# expansion.net
KiCad netlist of a schematic drawn in EAGLE
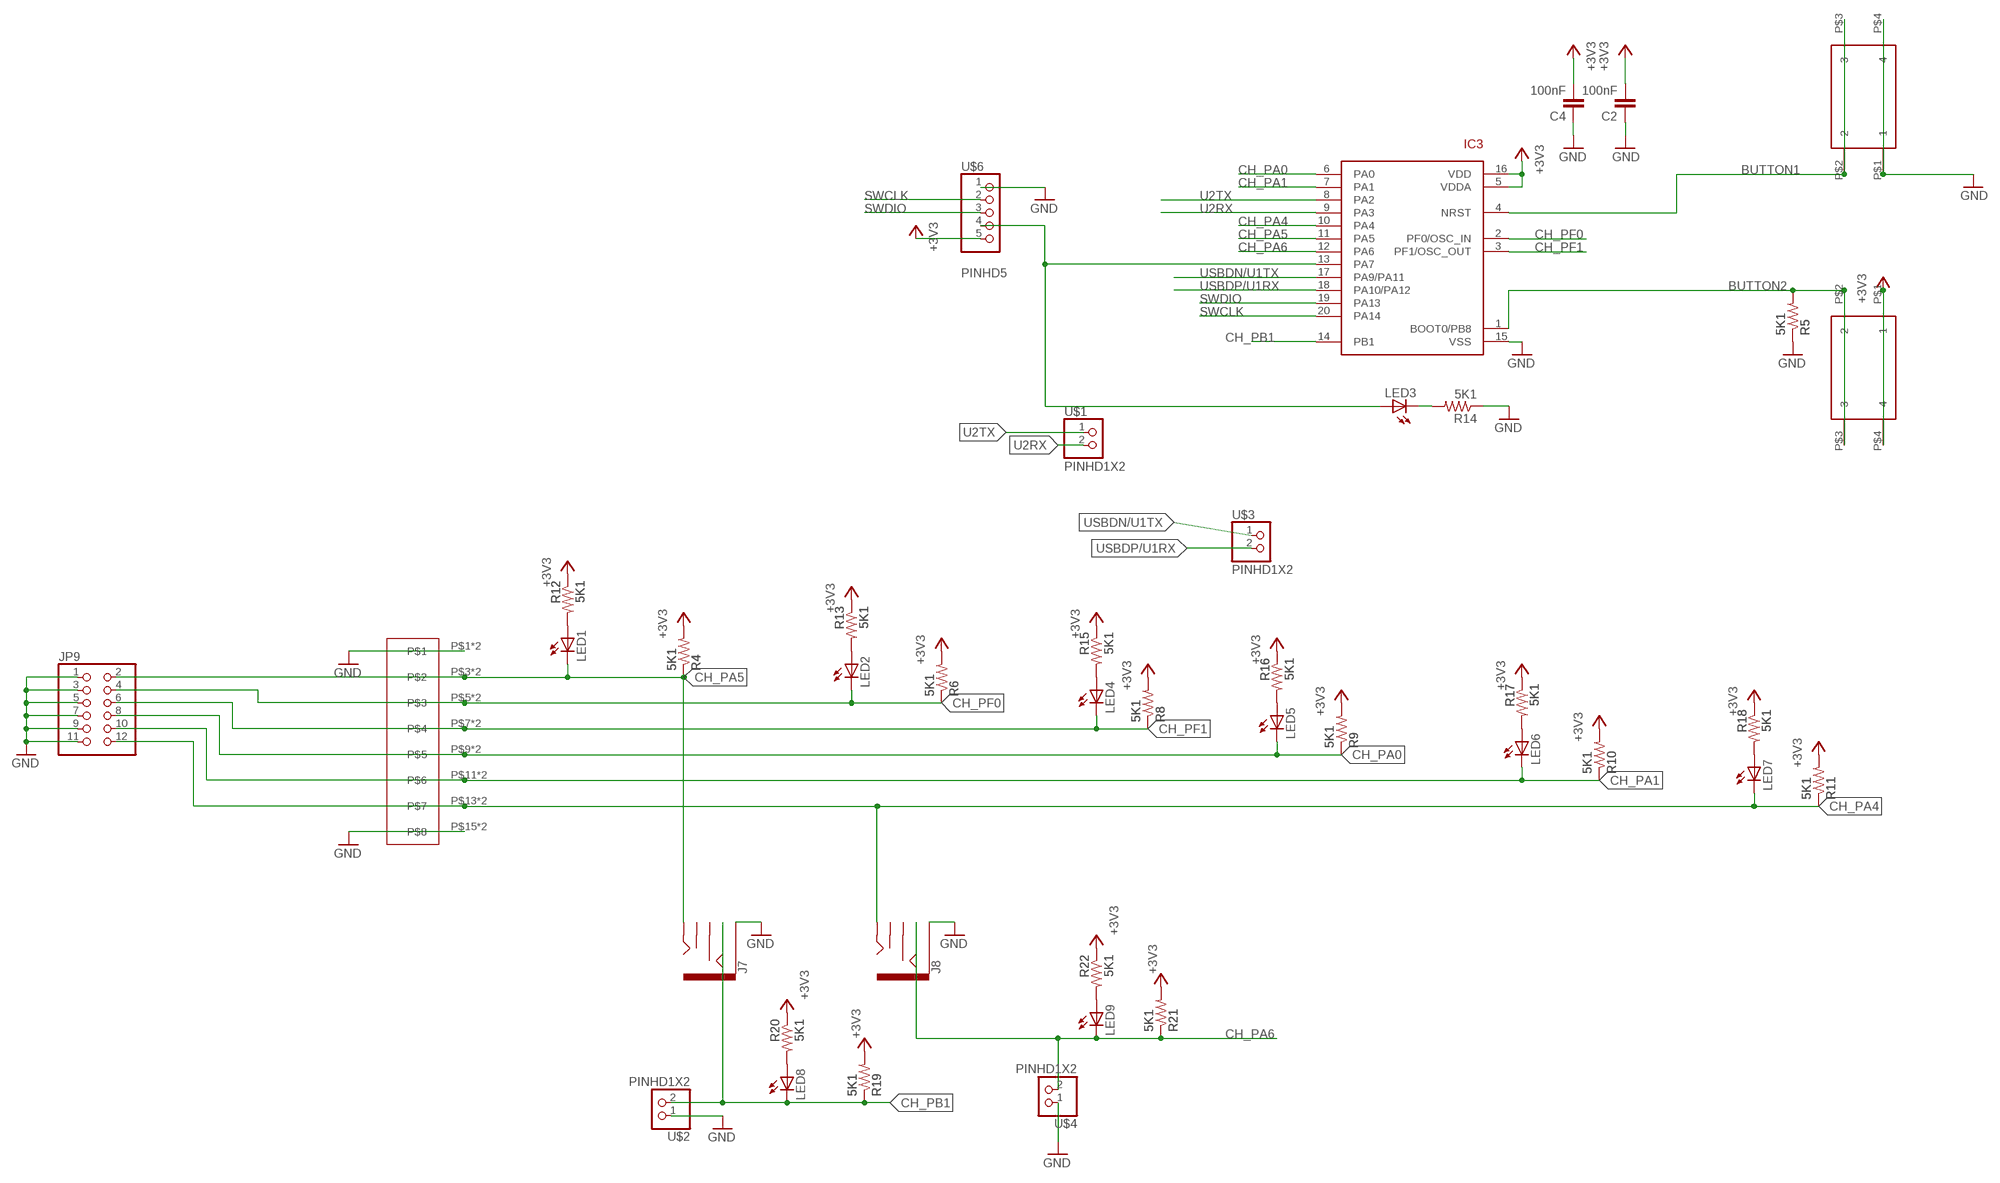
[diagram p0: schematic, sheet 1, part 1 of 2]
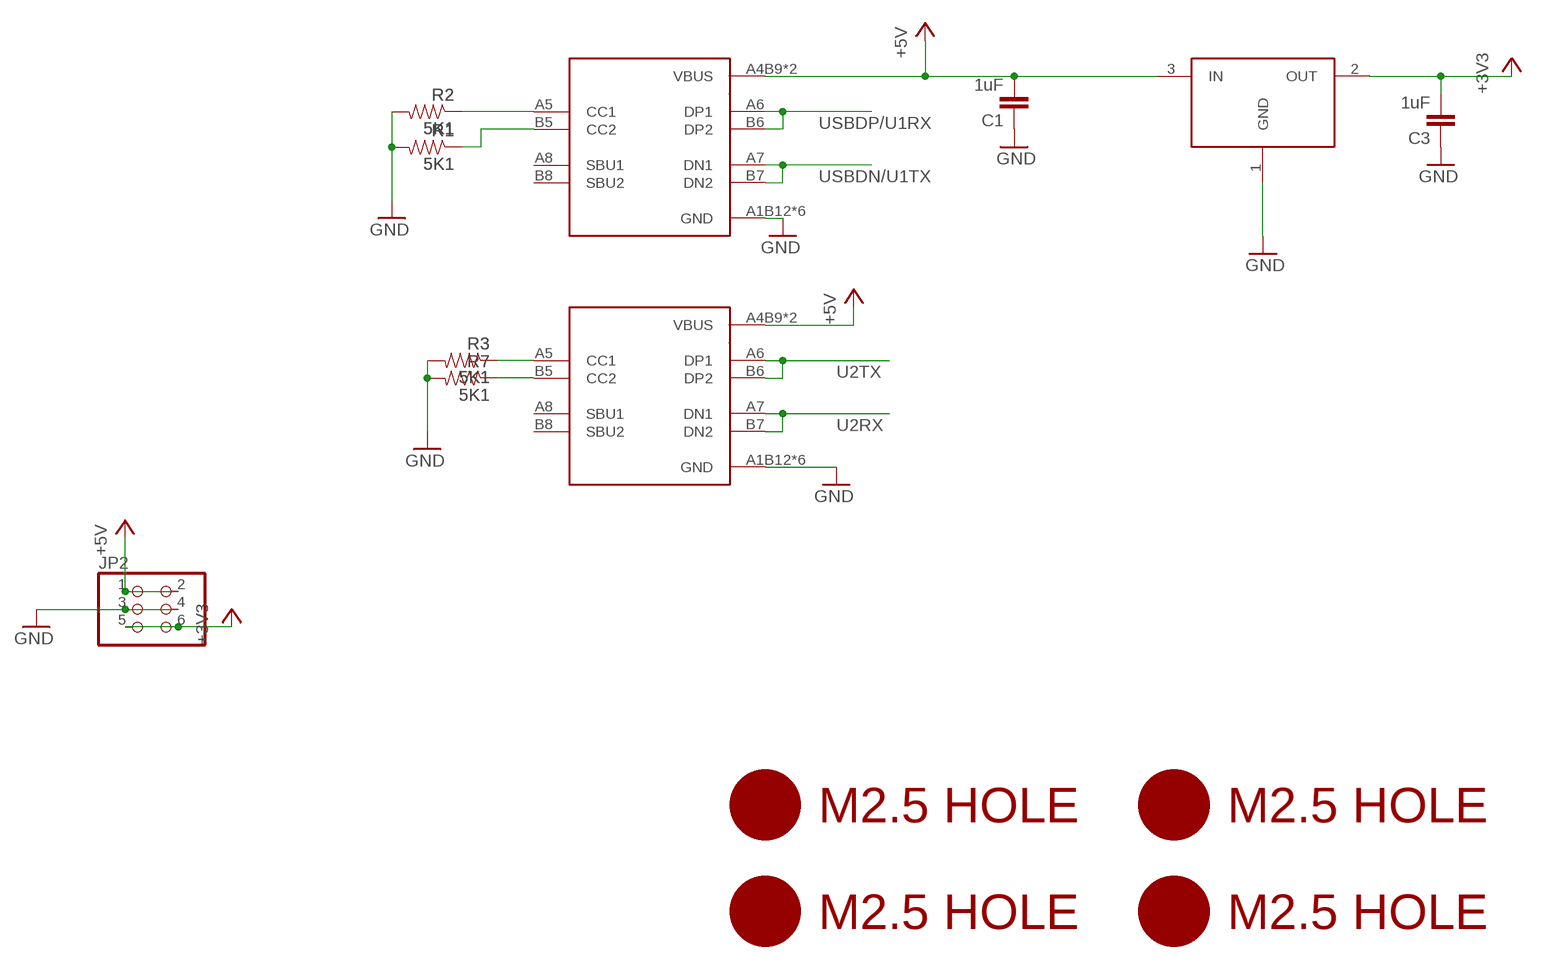
[diagram p1: schematic, sheet 1, part 2 of 2]

(export (version "E")
  (design (tool "Eeschema 10.0.6"))
  (components
    (comp (ref "C1")
      (value "1uF")
      (footprint "eagle-import:0805")
      (libsource (lib "eagle-import") (part "CAP0805"))
    )
    (comp (ref "C2")
      (value "100nF")
      (footprint "eagle-import:0805")
      (libsource (lib "eagle-import") (part "CAP0805"))
    )
    (comp (ref "C3")
      (value "1uF")
      (footprint "eagle-import:0805")
      (libsource (lib "eagle-import") (part "CAP0805"))
    )
    (comp (ref "C4")
      (value "100nF")
      (footprint "eagle-import:0805")
      (libsource (lib "eagle-import") (part "CAP0805"))
    )
    (comp (ref "IC3")
      (value "STM32F042F4")
      (footprint "eagle-import:TSSOP20")
      (libsource (lib "eagle-import") (part "STM32F042F4"))
    )
    (comp (ref "J7")
      (value "AUDIO_JACK_3.5MM_PTH")
      (footprint "eagle-import:AUDIO-JACK")
      (libsource (lib "eagle-import") (part "AUDIO_JACK_3.5MM_PTH"))
    )
    (comp (ref "J8")
      (value "AUDIO_JACK_3.5MM_PTH")
      (footprint "eagle-import:AUDIO-JACK")
      (libsource (lib "eagle-import") (part "AUDIO_JACK_3.5MM_PTH"))
    )
    (comp (ref "JP2")
      (value "PINHD-2X3")
      (footprint "eagle-import:2X03")
      (libsource (lib "eagle-import") (part "PINHD-2X3"))
    )
    (comp (ref "JP9")
      (value "PINHD-2X6")
      (footprint "eagle-import:2X06")
      (libsource (lib "eagle-import") (part "PINHD-2X6"))
    )
    (comp (ref "LED1")
      (value "LEDCHIP-LED0805")
      (footprint "eagle-import:CHIP-LED0805")
      (libsource (lib "eagle-import") (part "LEDCHIP-LED0805"))
    )
    (comp (ref "LED2")
      (value "LEDCHIP-LED0805")
      (footprint "eagle-import:CHIP-LED0805")
      (libsource (lib "eagle-import") (part "LEDCHIP-LED0805"))
    )
    (comp (ref "LED3")
      (value "LEDCHIP-LED0805")
      (footprint "eagle-import:CHIP-LED0805")
      (libsource (lib "eagle-import") (part "LEDCHIP-LED0805"))
    )
    (comp (ref "LED4")
      (value "LEDCHIP-LED0805")
      (footprint "eagle-import:CHIP-LED0805")
      (libsource (lib "eagle-import") (part "LEDCHIP-LED0805"))
    )
    (comp (ref "LED5")
      (value "LEDCHIP-LED0805")
      (footprint "eagle-import:CHIP-LED0805")
      (libsource (lib "eagle-import") (part "LEDCHIP-LED0805"))
    )
    (comp (ref "LED6")
      (value "LEDCHIP-LED0805")
      (footprint "eagle-import:CHIP-LED0805")
      (libsource (lib "eagle-import") (part "LEDCHIP-LED0805"))
    )
    (comp (ref "LED7")
      (value "LEDCHIP-LED0805")
      (footprint "eagle-import:CHIP-LED0805")
      (libsource (lib "eagle-import") (part "LEDCHIP-LED0805"))
    )
    (comp (ref "LED8")
      (value "LEDCHIP-LED0805")
      (footprint "eagle-import:CHIP-LED0805")
      (libsource (lib "eagle-import") (part "LEDCHIP-LED0805"))
    )
    (comp (ref "LED9")
      (value "LEDCHIP-LED0805")
      (footprint "eagle-import:CHIP-LED0805")
      (libsource (lib "eagle-import") (part "LEDCHIP-LED0805"))
    )
    (comp (ref "R1")
      (value "5K1")
      (footprint "eagle-import:0805")
      (libsource (lib "eagle-import") (part "joyAnalog_RESISTOR0805-RES"))
    )
    (comp (ref "R2")
      (value "5K1")
      (footprint "eagle-import:0805")
      (libsource (lib "eagle-import") (part "joyAnalog_RESISTOR0805-RES"))
    )
    (comp (ref "R3")
      (value "5K1")
      (footprint "eagle-import:0805")
      (libsource (lib "eagle-import") (part "joyAnalog_RESISTOR0805-RES"))
    )
    (comp (ref "R4")
      (value "5K1")
      (footprint "eagle-import:0805")
      (libsource (lib "eagle-import") (part "joyAnalog_RESISTOR0805-RES"))
    )
    (comp (ref "R5")
      (value "5K1")
      (footprint "eagle-import:0805")
      (libsource (lib "eagle-import") (part "joyAnalog_RESISTOR0805-RES"))
    )
    (comp (ref "R6")
      (value "5K1")
      (footprint "eagle-import:0805")
      (libsource (lib "eagle-import") (part "joyAnalog_RESISTOR0805-RES"))
    )
    (comp (ref "R7")
      (value "5K1")
      (footprint "eagle-import:0805")
      (libsource (lib "eagle-import") (part "joyAnalog_RESISTOR0805-RES"))
    )
    (comp (ref "R8")
      (value "5K1")
      (footprint "eagle-import:0805")
      (libsource (lib "eagle-import") (part "joyAnalog_RESISTOR0805-RES"))
    )
    (comp (ref "R9")
      (value "5K1")
      (footprint "eagle-import:0805")
      (libsource (lib "eagle-import") (part "joyAnalog_RESISTOR0805-RES"))
    )
    (comp (ref "R10")
      (value "5K1")
      (footprint "eagle-import:0805")
      (libsource (lib "eagle-import") (part "joyAnalog_RESISTOR0805-RES"))
    )
    (comp (ref "R11")
      (value "5K1")
      (footprint "eagle-import:0805")
      (libsource (lib "eagle-import") (part "joyAnalog_RESISTOR0805-RES"))
    )
    (comp (ref "R12")
      (value "5K1")
      (footprint "eagle-import:0805")
      (libsource (lib "eagle-import") (part "joyAnalog_RESISTOR0805-RES"))
    )
    (comp (ref "R13")
      (value "5K1")
      (footprint "eagle-import:0805")
      (libsource (lib "eagle-import") (part "joyAnalog_RESISTOR0805-RES"))
    )
    (comp (ref "R14")
      (value "5K1")
      (footprint "eagle-import:0805")
      (libsource (lib "eagle-import") (part "RESISTOR0805-RES"))
    )
    (comp (ref "R15")
      (value "5K1")
      (footprint "eagle-import:0805")
      (libsource (lib "eagle-import") (part "joyAnalog_RESISTOR0805-RES"))
    )
    (comp (ref "R16")
      (value "5K1")
      (footprint "eagle-import:0805")
      (libsource (lib "eagle-import") (part "joyAnalog_RESISTOR0805-RES"))
    )
    (comp (ref "R17")
      (value "5K1")
      (footprint "eagle-import:0805")
      (libsource (lib "eagle-import") (part "joyAnalog_RESISTOR0805-RES"))
    )
    (comp (ref "R18")
      (value "5K1")
      (footprint "eagle-import:0805")
      (libsource (lib "eagle-import") (part "joyAnalog_RESISTOR0805-RES"))
    )
    (comp (ref "R19")
      (value "5K1")
      (footprint "eagle-import:0805")
      (libsource (lib "eagle-import") (part "joyAnalog_RESISTOR0805-RES"))
    )
    (comp (ref "R20")
      (value "5K1")
      (footprint "eagle-import:0805")
      (libsource (lib "eagle-import") (part "joyAnalog_RESISTOR0805-RES"))
    )
    (comp (ref "R21")
      (value "5K1")
      (footprint "eagle-import:0805")
      (libsource (lib "eagle-import") (part "joyAnalog_RESISTOR0805-RES"))
    )
    (comp (ref "R22")
      (value "5K1")
      (footprint "eagle-import:0805")
      (libsource (lib "eagle-import") (part "joyAnalog_RESISTOR0805-RES"))
    )
    (comp (ref "SW3")
      (value "324_SW")
      (footprint "eagle-import:342_SWICH_FOOT")
      (libsource (lib "eagle-import") (part "324_SW"))
    )
    (comp (ref "SW4")
      (value "324_SW")
      (footprint "eagle-import:342_SWICH_FOOT")
      (libsource (lib "eagle-import") (part "324_SW"))
    )
    (comp (ref "U$1")
      (value "PINHD1X2")
      (footprint "eagle-import:1X02")
      (libsource (lib "eagle-import") (part "PINHD1X2"))
    )
    (comp (ref "U$2")
      (value "PINHD1X2")
      (footprint "eagle-import:1X02")
      (libsource (lib "eagle-import") (part "PINHD1X2"))
    )
    (comp (ref "U$3")
      (value "PINHD1X2")
      (footprint "eagle-import:1X02")
      (libsource (lib "eagle-import") (part "PINHD1X2"))
    )
    (comp (ref "U$4")
      (value "PINHD1X2")
      (footprint "eagle-import:1X02")
      (libsource (lib "eagle-import") (part "PINHD1X2"))
    )
    (comp (ref "U$6")
      (value "PINHD5")
      (footprint "eagle-import:1X05")
      (libsource (lib "eagle-import") (part "PINHD5"))
    )
    (comp (ref "U$8")
      (value "M2.5HOLE")
      (footprint "eagle-import:M2.5HOLE")
      (libsource (lib "eagle-import") (part "M2.5HOLE"))
    )
    (comp (ref "U$9")
      (value "M2.5HOLE")
      (footprint "eagle-import:M2.5HOLE")
      (libsource (lib "eagle-import") (part "M2.5HOLE"))
    )
    (comp (ref "U$10")
      (value "M2.5HOLE")
      (footprint "eagle-import:M2.5HOLE")
      (libsource (lib "eagle-import") (part "M2.5HOLE"))
    )
    (comp (ref "U$11")
      (value "M2.5HOLE")
      (footprint "eagle-import:M2.5HOLE")
      (libsource (lib "eagle-import") (part "M2.5HOLE"))
    )
    (comp (ref "U$14")
      (value "DG2204R-5.0-8DG2204-8")
      (footprint "eagle-import:DG2204R-8")
      (libsource (lib "eagle-import") (part "DG2204R-5.0-8DG2204-8"))
    )
    (comp (ref "U1")
      (value "USBC_16P")
      (footprint "eagle-import:USBC_16P_FOOT")
      (libsource (lib "eagle-import") (part "USBC_16P"))
    )
    (comp (ref "U2")
      (value "USBC_16P")
      (footprint "eagle-import:USBC_16P_FOOT")
      (libsource (lib "eagle-import") (part "USBC_16P"))
    )
    (comp (ref "U4")
      (value "XC6206_DEV")
      (footprint "eagle-import:SOT23R_INFINEON")
      (libsource (lib "eagle-import") (part "XC6206_DEV"))
    )
  )
  (nets
    (net (code "1") (name "+3V3") (class "Default")
      (node (ref "C2") (pin "2") (pinfunction "2_2") (pintype "passive"))
      (node (ref "C3") (pin "2") (pinfunction "2_2") (pintype "passive"))
      (node (ref "C4") (pin "2") (pinfunction "2_2") (pintype "passive"))
      (node (ref "IC3") (pin "16") (pinfunction "VDD_16") (pintype "bidirectional"))
      (node (ref "IC3") (pin "5") (pinfunction "VDDA_5") (pintype "bidirectional"))
      (node (ref "JP2") (pin "5") (pinfunction "5_5") (pintype "passive"))
      (node (ref "JP2") (pin "6") (pinfunction "6_6") (pintype "passive"))
      (node (ref "R10") (pin "2") (pinfunction "2_2") (pintype "passive"))
      (node (ref "R11") (pin "2") (pinfunction "2_2") (pintype "passive"))
      (node (ref "R12") (pin "1") (pinfunction "1_1") (pintype "passive"))
      (node (ref "R13") (pin "1") (pinfunction "1_1") (pintype "passive"))
      (node (ref "R15") (pin "1") (pinfunction "1_1") (pintype "passive"))
      (node (ref "R16") (pin "1") (pinfunction "1_1") (pintype "passive"))
      (node (ref "R17") (pin "1") (pinfunction "1_1") (pintype "passive"))
      (node (ref "R18") (pin "1") (pinfunction "1_1") (pintype "passive"))
      (node (ref "R19") (pin "2") (pinfunction "2_2") (pintype "passive"))
      (node (ref "R20") (pin "1") (pinfunction "1_1") (pintype "passive"))
      (node (ref "R21") (pin "2") (pinfunction "2_2") (pintype "passive"))
      (node (ref "R22") (pin "1") (pinfunction "1_1") (pintype "passive"))
      (node (ref "R4") (pin "2") (pinfunction "2_2") (pintype "passive"))
      (node (ref "R6") (pin "2") (pinfunction "2_2") (pintype "passive"))
      (node (ref "R8") (pin "2") (pinfunction "2_2") (pintype "passive"))
      (node (ref "R9") (pin "2") (pinfunction "2_2") (pintype "passive"))
      (node (ref "SW4") (pin "P$1") (pinfunction "1_P$1") (pintype "bidirectional"))
      (node (ref "SW4") (pin "P$4") (pinfunction "4_P$4") (pintype "bidirectional"))
      (node (ref "U$6") (pin "5") (pinfunction "5_5") (pintype "passive"))
      (node (ref "U4") (pin "2") (pinfunction "OUT_2") (pintype "bidirectional"))
    )
    (net (code "2") (name "+5V") (class "Default")
      (node (ref "C1") (pin "2") (pinfunction "2_2") (pintype "passive"))
      (node (ref "JP2") (pin "1") (pinfunction "1_1") (pintype "passive"))
      (node (ref "JP2") (pin "2") (pinfunction "2_2") (pintype "passive"))
      (node (ref "U1") (pin "A4B9") (pinfunction "VBUS_A4B9") (pintype "bidirectional"))
      (node (ref "U1") (pin "B4A9") (pinfunction "VBUS_B4A9") (pintype "bidirectional"))
      (node (ref "U2") (pin "A4B9") (pinfunction "VBUS_A4B9") (pintype "bidirectional"))
      (node (ref "U2") (pin "B4A9") (pinfunction "VBUS_B4A9") (pintype "bidirectional"))
      (node (ref "U4") (pin "3") (pinfunction "IN_3") (pintype "bidirectional"))
    )
    (net (code "3") (name "/BUTTON1") (class "Default")
      (node (ref "IC3") (pin "4") (pinfunction "NRST_4") (pintype "bidirectional"))
      (node (ref "SW3") (pin "P$2") (pinfunction "2_P$2") (pintype "bidirectional"))
      (node (ref "SW3") (pin "P$3") (pinfunction "3_P$3") (pintype "bidirectional"))
    )
    (net (code "4") (name "/BUTTON2") (class "Default")
      (node (ref "IC3") (pin "1") (pinfunction "BOOT0/PB8_1") (pintype "bidirectional"))
      (node (ref "R5") (pin "2") (pinfunction "2_2") (pintype "passive"))
      (node (ref "SW4") (pin "P$2") (pinfunction "2_P$2") (pintype "bidirectional"))
      (node (ref "SW4") (pin "P$3") (pinfunction "3_P$3") (pintype "bidirectional"))
    )
    (net (code "5") (name "/CH_PA6") (class "Default")
      (node (ref "IC3") (pin "12") (pinfunction "PA6_12") (pintype "bidirectional"))
      (node (ref "J8") (pin "RING") (pinfunction "RING_RING") (pintype "bidirectional"))
      (node (ref "LED9") (pin "C") (pinfunction "C_C") (pintype "passive"))
      (node (ref "R21") (pin "1") (pinfunction "1_1") (pintype "passive"))
      (node (ref "U$4") (pin "2") (pinfunction "2_2") (pintype "passive"))
    )
    (net (code "6") (name "/SWCLK") (class "Default")
      (node (ref "IC3") (pin "20") (pinfunction "PA14_20") (pintype "bidirectional"))
      (node (ref "U$6") (pin "2") (pinfunction "2_2") (pintype "passive"))
    )
    (net (code "7") (name "/SWDIO") (class "Default")
      (node (ref "IC3") (pin "19") (pinfunction "PA13_19") (pintype "bidirectional"))
      (node (ref "U$6") (pin "3") (pinfunction "3_3") (pintype "passive"))
    )
    (net (code "8") (name "CH_PA0") (class "Default")
      (node (ref "IC3") (pin "6") (pinfunction "PA0_6") (pintype "bidirectional"))
      (node (ref "JP9") (pin "8") (pinfunction "8_8") (pintype "passive"))
      (node (ref "LED5") (pin "C") (pinfunction "C_C") (pintype "passive"))
      (node (ref "R9") (pin "1") (pinfunction "1_1") (pintype "passive"))
      (node (ref "U$14") (pin "P$10") (pinfunction "P$5_P$10") (pintype "bidirectional"))
      (node (ref "U$14") (pin "P$9") (pinfunction "P$5_P$9") (pintype "bidirectional"))
    )
    (net (code "9") (name "CH_PA1") (class "Default")
      (node (ref "IC3") (pin "7") (pinfunction "PA1_7") (pintype "bidirectional"))
      (node (ref "JP9") (pin "10") (pinfunction "10_10") (pintype "passive"))
      (node (ref "LED6") (pin "C") (pinfunction "C_C") (pintype "passive"))
      (node (ref "R10") (pin "1") (pinfunction "1_1") (pintype "passive"))
      (node (ref "U$14") (pin "P$11") (pinfunction "P$6_P$11") (pintype "bidirectional"))
      (node (ref "U$14") (pin "P$12") (pinfunction "P$6_P$12") (pintype "bidirectional"))
    )
    (net (code "10") (name "CH_PA4") (class "Default")
      (node (ref "IC3") (pin "10") (pinfunction "PA4_10") (pintype "bidirectional"))
      (node (ref "J8") (pin "TIP") (pinfunction "TIP_TIP") (pintype "bidirectional"))
      (node (ref "JP9") (pin "12") (pinfunction "12_12") (pintype "passive"))
      (node (ref "LED7") (pin "C") (pinfunction "C_C") (pintype "passive"))
      (node (ref "R11") (pin "1") (pinfunction "1_1") (pintype "passive"))
      (node (ref "U$14") (pin "P$13") (pinfunction "P$7_P$13") (pintype "bidirectional"))
      (node (ref "U$14") (pin "P$14") (pinfunction "P$7_P$14") (pintype "bidirectional"))
    )
    (net (code "11") (name "CH_PA5") (class "Default")
      (node (ref "IC3") (pin "11") (pinfunction "PA5_11") (pintype "bidirectional"))
      (node (ref "J7") (pin "TIP") (pinfunction "TIP_TIP") (pintype "bidirectional"))
      (node (ref "JP9") (pin "2") (pinfunction "2_2") (pintype "passive"))
      (node (ref "LED1") (pin "C") (pinfunction "C_C") (pintype "passive"))
      (node (ref "R4") (pin "1") (pinfunction "1_1") (pintype "passive"))
      (node (ref "U$14") (pin "P$3") (pinfunction "P$2_P$3") (pintype "bidirectional"))
      (node (ref "U$14") (pin "P$4") (pinfunction "P$2_P$4") (pintype "bidirectional"))
    )
    (net (code "12") (name "CH_PB1") (class "Default")
      (node (ref "IC3") (pin "14") (pinfunction "PB1_14") (pintype "bidirectional"))
      (node (ref "J7") (pin "RING") (pinfunction "RING_RING") (pintype "bidirectional"))
      (node (ref "LED8") (pin "C") (pinfunction "C_C") (pintype "passive"))
      (node (ref "R19") (pin "1") (pinfunction "1_1") (pintype "passive"))
      (node (ref "U$2") (pin "2") (pinfunction "2_2") (pintype "passive"))
    )
    (net (code "13") (name "CH_PF0") (class "Default")
      (node (ref "IC3") (pin "2") (pinfunction "PF0/OSC_IN_2") (pintype "bidirectional"))
      (node (ref "JP9") (pin "4") (pinfunction "4_4") (pintype "passive"))
      (node (ref "LED2") (pin "C") (pinfunction "C_C") (pintype "passive"))
      (node (ref "R6") (pin "1") (pinfunction "1_1") (pintype "passive"))
      (node (ref "U$14") (pin "P$5") (pinfunction "P$3_P$5") (pintype "bidirectional"))
      (node (ref "U$14") (pin "P$6") (pinfunction "P$3_P$6") (pintype "bidirectional"))
    )
    (net (code "14") (name "CH_PF1") (class "Default")
      (node (ref "IC3") (pin "3") (pinfunction "PF1/OSC_OUT_3") (pintype "bidirectional"))
      (node (ref "JP9") (pin "6") (pinfunction "6_6") (pintype "passive"))
      (node (ref "LED4") (pin "C") (pinfunction "C_C") (pintype "passive"))
      (node (ref "R8") (pin "1") (pinfunction "1_1") (pintype "passive"))
      (node (ref "U$14") (pin "P$7") (pinfunction "P$4_P$7") (pintype "bidirectional"))
      (node (ref "U$14") (pin "P$8") (pinfunction "P$4_P$8") (pintype "bidirectional"))
    )
    (net (code "15") (name "GND") (class "Default")
      (node (ref "C1") (pin "1") (pinfunction "1_1") (pintype "passive"))
      (node (ref "C2") (pin "1") (pinfunction "1_1") (pintype "passive"))
      (node (ref "C3") (pin "1") (pinfunction "1_1") (pintype "passive"))
      (node (ref "C4") (pin "1") (pinfunction "1_1") (pintype "passive"))
      (node (ref "IC3") (pin "15") (pinfunction "VSS_15") (pintype "bidirectional"))
      (node (ref "J7") (pin "SLEEVE") (pinfunction "SLEEVE_SLEEVE") (pintype "bidirectional"))
      (node (ref "J8") (pin "SLEEVE") (pinfunction "SLEEVE_SLEEVE") (pintype "bidirectional"))
      (node (ref "JP2") (pin "3") (pinfunction "3_3") (pintype "passive"))
      (node (ref "JP2") (pin "4") (pinfunction "4_4") (pintype "passive"))
      (node (ref "JP9") (pin "1") (pinfunction "1_1") (pintype "passive"))
      (node (ref "JP9") (pin "11") (pinfunction "11_11") (pintype "passive"))
      (node (ref "JP9") (pin "3") (pinfunction "3_3") (pintype "passive"))
      (node (ref "JP9") (pin "5") (pinfunction "5_5") (pintype "passive"))
      (node (ref "JP9") (pin "7") (pinfunction "7_7") (pintype "passive"))
      (node (ref "JP9") (pin "9") (pinfunction "9_9") (pintype "passive"))
      (node (ref "R1") (pin "2") (pinfunction "2_2") (pintype "passive"))
      (node (ref "R14") (pin "1") (pinfunction "1_1") (pintype "passive"))
      (node (ref "R2") (pin "2") (pinfunction "2_2") (pintype "passive"))
      (node (ref "R3") (pin "2") (pinfunction "2_2") (pintype "passive"))
      (node (ref "R5") (pin "1") (pinfunction "1_1") (pintype "passive"))
      (node (ref "R7") (pin "2") (pinfunction "2_2") (pintype "passive"))
      (node (ref "SW3") (pin "P$1") (pinfunction "1_P$1") (pintype "bidirectional"))
      (node (ref "SW3") (pin "P$4") (pinfunction "4_P$4") (pintype "bidirectional"))
      (node (ref "U$14") (pin "P$1") (pinfunction "P$1_P$1") (pintype "bidirectional"))
      (node (ref "U$14") (pin "P$15") (pinfunction "P$8_P$15") (pintype "bidirectional"))
      (node (ref "U$14") (pin "P$16") (pinfunction "P$8_P$16") (pintype "bidirectional"))
      (node (ref "U$14") (pin "P$2") (pinfunction "P$1_P$2") (pintype "bidirectional"))
      (node (ref "U$2") (pin "1") (pinfunction "1_1") (pintype "passive"))
      (node (ref "U$4") (pin "1") (pinfunction "1_1") (pintype "passive"))
      (node (ref "U$6") (pin "1") (pinfunction "1_1") (pintype "passive"))
      (node (ref "U1") (pin "A1B12") (pinfunction "GND_A1B12") (pintype "bidirectional"))
      (node (ref "U1") (pin "B11A12") (pinfunction "GND_B11A12") (pintype "bidirectional"))
      (node (ref "U1") (pin "P$13") (pinfunction "GND_P$13") (pintype "bidirectional"))
      (node (ref "U1") (pin "P$14") (pinfunction "GND_P$14") (pintype "bidirectional"))
      (node (ref "U1") (pin "P$15") (pinfunction "GND_P$15") (pintype "bidirectional"))
      (node (ref "U1") (pin "P$16") (pinfunction "GND_P$16") (pintype "bidirectional"))
      (node (ref "U2") (pin "A1B12") (pinfunction "GND_A1B12") (pintype "bidirectional"))
      (node (ref "U2") (pin "B11A12") (pinfunction "GND_B11A12") (pintype "bidirectional"))
      (node (ref "U2") (pin "P$13") (pinfunction "GND_P$13") (pintype "bidirectional"))
      (node (ref "U2") (pin "P$14") (pinfunction "GND_P$14") (pintype "bidirectional"))
      (node (ref "U2") (pin "P$15") (pinfunction "GND_P$15") (pintype "bidirectional"))
      (node (ref "U2") (pin "P$16") (pinfunction "GND_P$16") (pintype "bidirectional"))
      (node (ref "U4") (pin "1") (pinfunction "GND_1") (pintype "bidirectional"))
    )
    (net (code "16") (name "Net-(IC3-PA7)") (class "Default")
      (node (ref "IC3") (pin "13") (pinfunction "PA7_13") (pintype "bidirectional"))
      (node (ref "LED3") (pin "A") (pinfunction "A_A") (pintype "passive"))
      (node (ref "U$6") (pin "4") (pinfunction "4_4") (pintype "passive"))
    )
    (net (code "17") (name "Net-(LED1-PadA)") (class "Default")
      (node (ref "LED1") (pin "A") (pinfunction "A_A") (pintype "passive"))
      (node (ref "R12") (pin "2") (pinfunction "2_2") (pintype "passive"))
    )
    (net (code "18") (name "Net-(LED2-PadA)") (class "Default")
      (node (ref "LED2") (pin "A") (pinfunction "A_A") (pintype "passive"))
      (node (ref "R13") (pin "2") (pinfunction "2_2") (pintype "passive"))
    )
    (net (code "19") (name "Net-(LED3-PadC)") (class "Default")
      (node (ref "LED3") (pin "C") (pinfunction "C_C") (pintype "passive"))
      (node (ref "R14") (pin "2") (pinfunction "2_2") (pintype "passive"))
    )
    (net (code "20") (name "Net-(LED4-PadA)") (class "Default")
      (node (ref "LED4") (pin "A") (pinfunction "A_A") (pintype "passive"))
      (node (ref "R15") (pin "2") (pinfunction "2_2") (pintype "passive"))
    )
    (net (code "21") (name "Net-(LED5-PadA)") (class "Default")
      (node (ref "LED5") (pin "A") (pinfunction "A_A") (pintype "passive"))
      (node (ref "R16") (pin "2") (pinfunction "2_2") (pintype "passive"))
    )
    (net (code "22") (name "Net-(LED6-PadA)") (class "Default")
      (node (ref "LED6") (pin "A") (pinfunction "A_A") (pintype "passive"))
      (node (ref "R17") (pin "2") (pinfunction "2_2") (pintype "passive"))
    )
    (net (code "23") (name "Net-(LED7-PadA)") (class "Default")
      (node (ref "LED7") (pin "A") (pinfunction "A_A") (pintype "passive"))
      (node (ref "R18") (pin "2") (pinfunction "2_2") (pintype "passive"))
    )
    (net (code "24") (name "Net-(LED8-PadA)") (class "Default")
      (node (ref "LED8") (pin "A") (pinfunction "A_A") (pintype "passive"))
      (node (ref "R20") (pin "2") (pinfunction "2_2") (pintype "passive"))
    )
    (net (code "25") (name "Net-(LED9-PadA)") (class "Default")
      (node (ref "LED9") (pin "A") (pinfunction "A_A") (pintype "passive"))
      (node (ref "R22") (pin "2") (pinfunction "2_2") (pintype "passive"))
    )
    (net (code "26") (name "Net-(U1-CC1)") (class "Default")
      (node (ref "R3") (pin "1") (pinfunction "1_1") (pintype "passive"))
      (node (ref "U1") (pin "A5") (pinfunction "CC1_A5") (pintype "bidirectional"))
    )
    (net (code "27") (name "Net-(U1-CC2)") (class "Default")
      (node (ref "R7") (pin "1") (pinfunction "1_1") (pintype "passive"))
      (node (ref "U1") (pin "B5") (pinfunction "CC2_B5") (pintype "bidirectional"))
    )
    (net (code "28") (name "Net-(U2-CC1)") (class "Default")
      (node (ref "R2") (pin "1") (pinfunction "1_1") (pintype "passive"))
      (node (ref "U2") (pin "A5") (pinfunction "CC1_A5") (pintype "bidirectional"))
    )
    (net (code "29") (name "Net-(U2-CC2)") (class "Default")
      (node (ref "R1") (pin "1") (pinfunction "1_1") (pintype "passive"))
      (node (ref "U2") (pin "B5") (pinfunction "CC2_B5") (pintype "bidirectional"))
    )
    (net (code "30") (name "U2RX") (class "Default")
      (node (ref "IC3") (pin "9") (pinfunction "PA3_9") (pintype "bidirectional"))
      (node (ref "U$1") (pin "2") (pinfunction "2_2") (pintype "passive"))
      (node (ref "U1") (pin "A7") (pinfunction "DN1_A7") (pintype "bidirectional"))
      (node (ref "U1") (pin "B7") (pinfunction "DN2_B7") (pintype "bidirectional"))
    )
    (net (code "31") (name "U2TX") (class "Default")
      (node (ref "IC3") (pin "8") (pinfunction "PA2_8") (pintype "bidirectional"))
      (node (ref "U$1") (pin "1") (pinfunction "1_1") (pintype "passive"))
      (node (ref "U1") (pin "A6") (pinfunction "DP1_A6") (pintype "bidirectional"))
      (node (ref "U1") (pin "B6") (pinfunction "DP2_B6") (pintype "bidirectional"))
    )
    (net (code "32") (name "USBDN{slash}U1TX") (class "Default")
      (node (ref "IC3") (pin "17") (pinfunction "PA9/PA11_17") (pintype "bidirectional"))
      (node (ref "U$3") (pin "1") (pinfunction "1_1") (pintype "passive"))
      (node (ref "U2") (pin "A7") (pinfunction "DN1_A7") (pintype "bidirectional"))
      (node (ref "U2") (pin "B7") (pinfunction "DN2_B7") (pintype "bidirectional"))
    )
    (net (code "33") (name "USBDP{slash}U1RX") (class "Default")
      (node (ref "IC3") (pin "18") (pinfunction "PA10/PA12_18") (pintype "bidirectional"))
      (node (ref "U$3") (pin "2") (pinfunction "2_2") (pintype "passive"))
      (node (ref "U2") (pin "A6") (pinfunction "DP1_A6") (pintype "bidirectional"))
      (node (ref "U2") (pin "B6") (pinfunction "DP2_B6") (pintype "bidirectional"))
    )
    (net (code "34") (name "unconnected-(J7-PadRSH)") (class "Default")
      (node (ref "J7") (pin "RSH") (pinfunction "RSH_RSH") (pintype "bidirectional"))
    )
    (net (code "35") (name "unconnected-(J7-PadTSH)") (class "Default")
      (node (ref "J7") (pin "TSH") (pinfunction "TSH_TSH") (pintype "bidirectional"))
    )
    (net (code "36") (name "unconnected-(J8-PadRSH)") (class "Default")
      (node (ref "J8") (pin "RSH") (pinfunction "RSH_RSH") (pintype "bidirectional"))
    )
    (net (code "37") (name "unconnected-(J8-PadTSH)") (class "Default")
      (node (ref "J8") (pin "TSH") (pinfunction "TSH_TSH") (pintype "bidirectional"))
    )
    (net (code "38") (name "unconnected-(U1-SBU1-PadA8)") (class "Default")
      (node (ref "U1") (pin "A8") (pinfunction "SBU1_A8") (pintype "bidirectional"))
    )
    (net (code "39") (name "unconnected-(U1-SBU2-PadB8)") (class "Default")
      (node (ref "U1") (pin "B8") (pinfunction "SBU2_B8") (pintype "bidirectional"))
    )
    (net (code "40") (name "unconnected-(U2-SBU1-PadA8)") (class "Default")
      (node (ref "U2") (pin "A8") (pinfunction "SBU1_A8") (pintype "bidirectional"))
    )
    (net (code "41") (name "unconnected-(U2-SBU2-PadB8)") (class "Default")
      (node (ref "U2") (pin "B8") (pinfunction "SBU2_B8") (pintype "bidirectional"))
    )
  )
)
